# main.net
KiCad netlist of a schematic drawn in Altium Designer
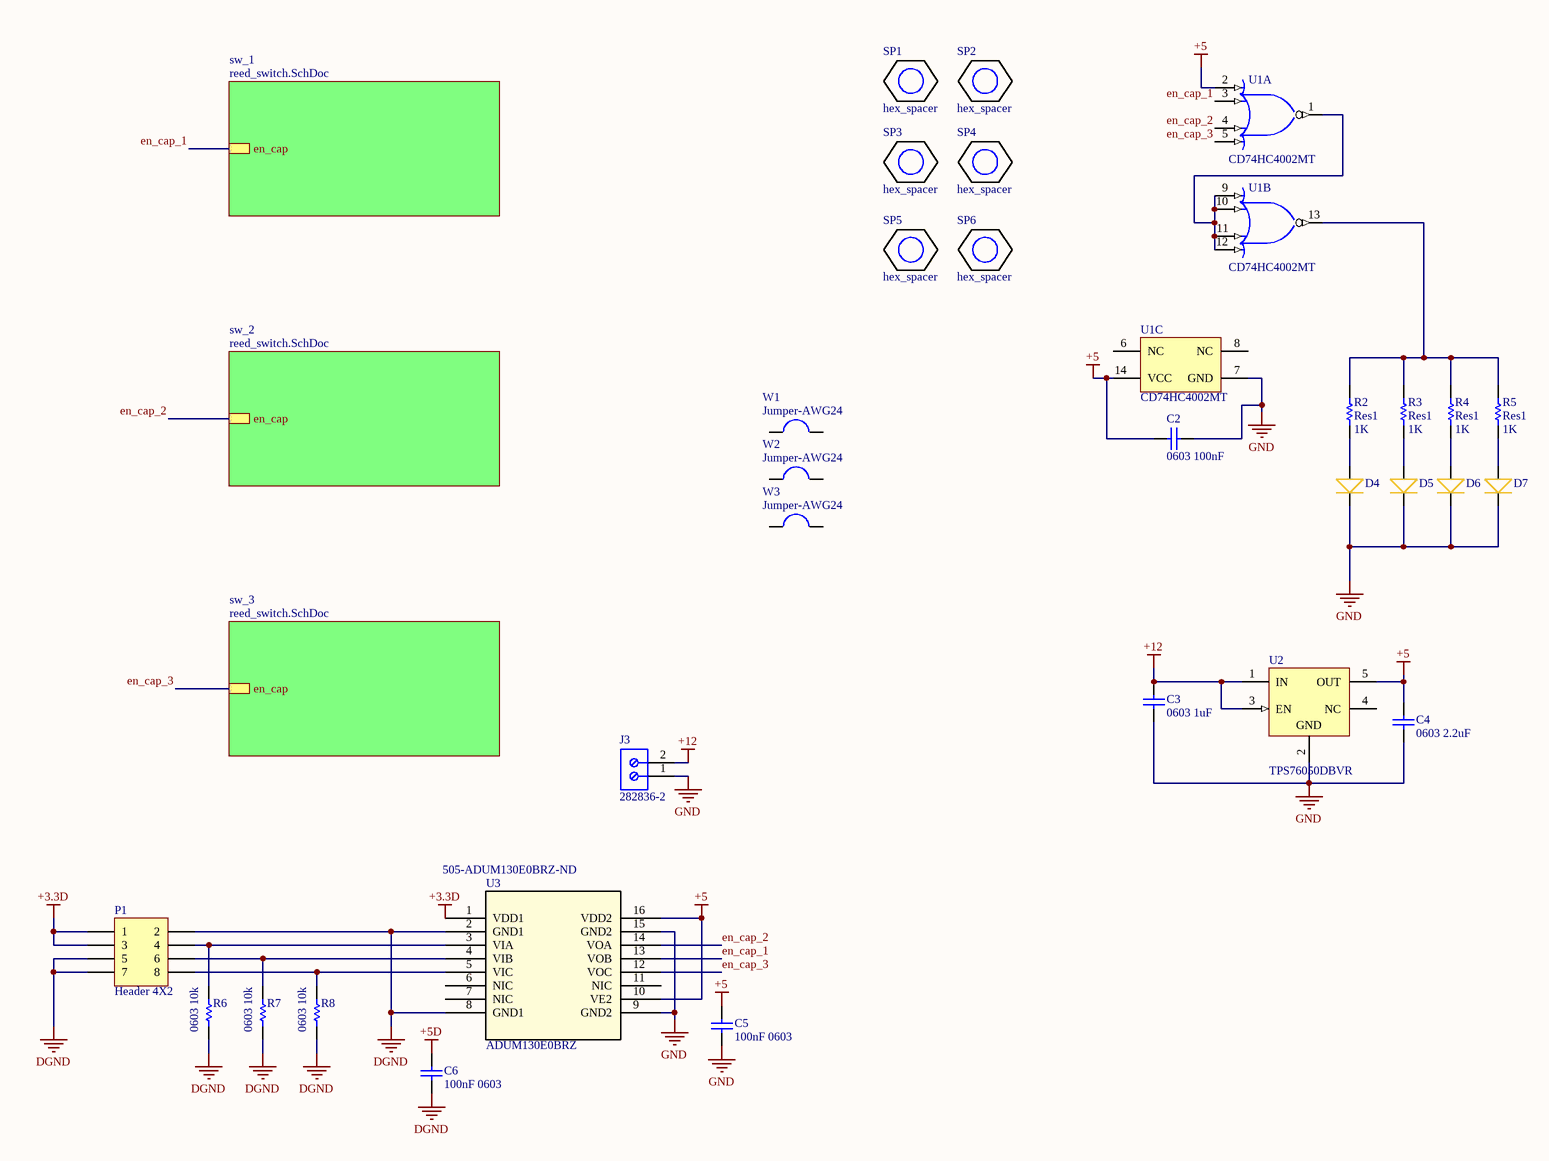
[diagram p0: main.SchDoc]

(export (version "E")
  (design (tool "Eeschema 10.0.6"))
  (components
    (comp (ref "C2")
      (value "0603 100nF")
      (footprint "CAP 0603_1608")
      (description "Capacitor")
      (fields (field (name "PUBLISHER") "Altium Limited"))
      (libsource (lib "Miscellaneous Devices") (part "Cap"))
    )
    (comp (ref "C3")
      (value "0603 1uF")
      (footprint "CAP 0603_1608")
      (description "Capacitor")
      (fields (field (name "PUBLISHER") "Altium Limited"))
      (libsource (lib "Miscellaneous Devices") (part "Cap"))
    )
    (comp (ref "C4")
      (value "0603 2.2uF")
      (footprint "CAP 0603_1608")
      (description "Capacitor")
      (fields (field (name "PUBLISHER") "Altium Limited"))
      (libsource (lib "Miscellaneous Devices") (part "Cap"))
    )
    (comp (ref "C5")
      (value "100nF 0603")
      (footprint "CAP 0603_1608")
      (description "Capacitor")
      (fields (field (name "PUBLISHER") "Altium Limited"))
      (libsource (lib "Miscellaneous Devices") (part "Cap"))
    )
    (comp (ref "C6")
      (value "100nF 0603")
      (footprint "CAP 0603_1608")
      (description "Capacitor")
      (fields (field (name "PUBLISHER") "Altium Limited"))
      (libsource (lib "Miscellaneous Devices") (part "Cap"))
    )
    (comp (ref "D4")
      (value "732-12018-1-ND")
      (footprint "LED_YELLOW_0603")
      (libsource (lib "coil_driver_lib") (part "led_yellow_0603"))
    )
    (comp (ref "D5")
      (value "732-12018-1-ND")
      (footprint "LED_YELLOW_0603")
      (libsource (lib "coil_driver_lib") (part "led_yellow_0603"))
    )
    (comp (ref "D6")
      (value "732-12018-1-ND")
      (footprint "LED_YELLOW_0603")
      (libsource (lib "coil_driver_lib") (part "led_yellow_0603"))
    )
    (comp (ref "D7")
      (value "732-12018-1-ND")
      (footprint "LED_YELLOW_0603")
      (libsource (lib "coil_driver_lib") (part "led_yellow_0603"))
    )
    (comp (ref "J3")
      (value "282836-2")
      (footprint "TECO-282836-2_V")
      (description "Female Header, Pitch 5 mm, 1 x 2 Position, Height 10 mm, Tail Length 3.5 mm, Rohs, Bulk")
      (fields (field (name "VOLTAGE") "300V") (field (name "MANUFACTURER") "TE Connectivity"))
      (libsource (lib "Altium Content Vault") (part "CN-1P-F-TB2"))
    )
    (comp (ref "P1")
      (value "Header 4X2")
      (footprint "HEADER_4_2")
      (description "Header, 4-Pin, Dual row")
      (fields (field (name "PUBLISHER") "Altium Limited"))
      (libsource (lib "Miscellaneous Connectors") (part "Header 4X2"))
    )
    (comp (ref "R2")
      (value "Res1")
      (footprint "RES 0603_1608")
      (description "Resistor")
      (fields (field (name "ALTIUM_VALUE") "1K") (field (name "PUBLISHER") "Altium Limited"))
      (libsource (lib "Miscellaneous Devices") (part "Res1"))
    )
    (comp (ref "R3")
      (value "Res1")
      (footprint "RES 0603_1608")
      (description "Resistor")
      (fields (field (name "ALTIUM_VALUE") "1K") (field (name "PUBLISHER") "Altium Limited"))
      (libsource (lib "Miscellaneous Devices") (part "Res1"))
    )
    (comp (ref "R4")
      (value "Res1")
      (footprint "RES 0603_1608")
      (description "Resistor")
      (fields (field (name "ALTIUM_VALUE") "1K") (field (name "PUBLISHER") "Altium Limited"))
      (libsource (lib "Miscellaneous Devices") (part "Res1"))
    )
    (comp (ref "R5")
      (value "Res1")
      (footprint "RES 0603_1608")
      (description "Resistor")
      (fields (field (name "ALTIUM_VALUE") "1K") (field (name "PUBLISHER") "Altium Limited"))
      (libsource (lib "Miscellaneous Devices") (part "Res1"))
    )
    (comp (ref "R6")
      (value "0603 10k")
      (footprint "RES 0603_1608")
      (description "Resistor")
      (fields (field (name "PUBLISHER") "Altium Limited"))
      (libsource (lib "Miscellaneous Devices") (part "Res1"))
    )
    (comp (ref "R7")
      (value "0603 10k")
      (footprint "RES 0603_1608")
      (description "Resistor")
      (fields (field (name "PUBLISHER") "Altium Limited"))
      (libsource (lib "Miscellaneous Devices") (part "Res1"))
    )
    (comp (ref "R8")
      (value "0603 10k")
      (footprint "RES 0603_1608")
      (description "Resistor")
      (fields (field (name "PUBLISHER") "Altium Limited"))
      (libsource (lib "Miscellaneous Devices") (part "Res1"))
    )
    (comp (ref "SP1")
      (value "hex_spacer")
      (footprint "hex_spacer")
      (libsource (lib "coil_driver_lib") (part "hex_spacer"))
    )
    (comp (ref "SP2")
      (value "hex_spacer")
      (footprint "hex_spacer")
      (libsource (lib "coil_driver_lib") (part "hex_spacer"))
    )
    (comp (ref "SP3")
      (value "hex_spacer")
      (footprint "hex_spacer")
      (libsource (lib "coil_driver_lib") (part "hex_spacer"))
    )
    (comp (ref "SP4")
      (value "hex_spacer")
      (footprint "hex_spacer")
      (libsource (lib "coil_driver_lib") (part "hex_spacer"))
    )
    (comp (ref "SP5")
      (value "hex_spacer")
      (footprint "hex_spacer")
      (libsource (lib "coil_driver_lib") (part "hex_spacer"))
    )
    (comp (ref "SP6")
      (value "hex_spacer")
      (footprint "hex_spacer")
      (libsource (lib "coil_driver_lib") (part "hex_spacer"))
    )
    (comp (ref "U1")
      (value "CD74HC4002MT")
      (footprint "D0014A_N")
      (description "High Speed CMOS Logic Dual 4-Input NOR Gates, D0014A, SMALL T&R")
      (fields
        (field (name "MANUFACTURER") "Texas Instruments")
        (field (name "GENERIC PART NUMBER") "CD74HC4002")
      )
      (libsource (lib "Altium Content Vault") (part "TI-CD_SNX4HC4002-14"))
    )
    (comp (ref "U2")
      (value "TPS76050DBVR")
      (footprint "DBV0005A_L")
      (fields (field (name "MANUFACTURER") "Texas Instruments"))
      (libsource (lib "Altium Content Vault") (part "TI-TXX7XXXX-5"))
    )
    (comp (ref "U3")
      (value "ADUM130E0BRZ")
      (footprint "R_16")
      (description "No Description Available")
      (fields
        (field (name "SUPPLIER PART NUMBER 1") "505-ADUM130E0BRZ-ND")
        (field (name "COPYRIGHT") "Copyright (C) 2021 Ultra Librarian. All rights reserved.")
      )
      (libsource (lib "ADUM130E0BRZ") (part "ADUM130E0BRZ"))
    )
    (comp (ref "W1")
      (value "wire_jumper")
      (footprint "wire_jumper")
      (libsource (lib "coil_driver_lib") (part "wire_jumper"))
    )
    (comp (ref "W2")
      (value "wire_jumper")
      (footprint "wire_jumper")
      (libsource (lib "coil_driver_lib") (part "wire_jumper"))
    )
    (comp (ref "W3")
      (value "wire_jumper")
      (footprint "wire_jumper")
      (libsource (lib "coil_driver_lib") (part "wire_jumper"))
    )
  )
  (nets
    (net (code "1") (name "+3.3D") (class "Default")
      (node (ref "P1") (pin "1") (pinfunction "1_1") (pintype "passive"))
      (node (ref "P1") (pin "3") (pinfunction "3_3") (pintype "passive"))
      (node (ref "U3") (pin "1") (pinfunction "VDD1_1") (pintype "passive"))
    )
    (net (code "2") (name "+5") (class "Default")
      (node (ref "C2") (pin "2") (pinfunction "2_2") (pintype "passive"))
      (node (ref "C4") (pin "2") (pinfunction "2_2") (pintype "passive"))
      (node (ref "C5") (pin "2") (pinfunction "2_2") (pintype "passive"))
      (node (ref "U1") (pin "14") (pinfunction "VCC_14") (pintype "power_in"))
      (node (ref "U1") (pin "2") (pinfunction "1A_2") (pintype "input"))
      (node (ref "U2") (pin "5") (pinfunction "OUT_5") (pintype "power_in"))
      (node (ref "U3") (pin "10") (pinfunction "VE2_10") (pintype "passive"))
      (node (ref "U3") (pin "16") (pinfunction "VDD2_16") (pintype "passive"))
    )
    (net (code "3") (name "+5D") (class "Default")
      (node (ref "C6") (pin "2") (pinfunction "2_2") (pintype "passive"))
    )
    (net (code "4") (name "+12") (class "Default")
      (node (ref "C3") (pin "2") (pinfunction "2_2") (pintype "passive"))
      (node (ref "J3") (pin "2") (pinfunction "2_2") (pintype "passive"))
      (node (ref "U2") (pin "1") (pinfunction "IN_1") (pintype "power_in"))
      (node (ref "U2") (pin "3") (pinfunction "EN_3") (pintype "input"))
    )
    (net (code "5") (name "/en_cap_1") (class "Default")
      (node (ref "U1") (pin "3") (pinfunction "1B_3") (pintype "input"))
      (node (ref "U3") (pin "13") (pinfunction "VOB_13") (pintype "passive"))
    )
    (net (code "6") (name "/en_cap_2") (class "Default")
      (node (ref "U1") (pin "4") (pinfunction "1C_4") (pintype "input"))
      (node (ref "U3") (pin "14") (pinfunction "VOA_14") (pintype "passive"))
    )
    (net (code "7") (name "/en_cap_3") (class "Default")
      (node (ref "U1") (pin "5") (pinfunction "1D_5") (pintype "input"))
      (node (ref "U3") (pin "12") (pinfunction "VOC_12") (pintype "passive"))
    )
    (net (code "8") (name "DGND") (class "Default")
      (node (ref "C6") (pin "1") (pinfunction "1_1") (pintype "passive"))
      (node (ref "P1") (pin "2") (pinfunction "2_2") (pintype "passive"))
      (node (ref "P1") (pin "5") (pinfunction "5_5") (pintype "passive"))
      (node (ref "P1") (pin "7") (pinfunction "7_7") (pintype "passive"))
      (node (ref "R6") (pin "1") (pinfunction "1_1") (pintype "passive"))
      (node (ref "R7") (pin "1") (pinfunction "1_1") (pintype "passive"))
      (node (ref "R8") (pin "1") (pinfunction "1_1") (pintype "passive"))
      (node (ref "U3") (pin "2") (pinfunction "GND1_2") (pintype "passive"))
      (node (ref "U3") (pin "8") (pinfunction "GND1_8") (pintype "passive"))
    )
    (net (code "9") (name "GND") (class "Default")
      (node (ref "C2") (pin "1") (pinfunction "1_1") (pintype "passive"))
      (node (ref "C3") (pin "1") (pinfunction "1_1") (pintype "passive"))
      (node (ref "C4") (pin "1") (pinfunction "1_1") (pintype "passive"))
      (node (ref "C5") (pin "1") (pinfunction "1_1") (pintype "passive"))
      (node (ref "D4") (pin "C") (pinfunction "C_C") (pintype "passive"))
      (node (ref "D5") (pin "C") (pinfunction "C_C") (pintype "passive"))
      (node (ref "D6") (pin "C") (pinfunction "C_C") (pintype "passive"))
      (node (ref "D7") (pin "C") (pinfunction "C_C") (pintype "passive"))
      (node (ref "J3") (pin "1") (pinfunction "1_1") (pintype "passive"))
      (node (ref "U1") (pin "7") (pinfunction "GND_7") (pintype "power_in"))
      (node (ref "U2") (pin "2") (pinfunction "GND_2") (pintype "power_in"))
      (node (ref "U3") (pin "15") (pinfunction "GND2_15") (pintype "passive"))
      (node (ref "U3") (pin "9") (pinfunction "GND2_9") (pintype "passive"))
    )
    (net (code "10") (name "Net-(D4-PadA)") (class "Default")
      (node (ref "D4") (pin "A") (pinfunction "A_A") (pintype "passive"))
      (node (ref "R2") (pin "1") (pinfunction "1_1") (pintype "passive"))
    )
    (net (code "11") (name "Net-(D5-PadA)") (class "Default")
      (node (ref "D5") (pin "A") (pinfunction "A_A") (pintype "passive"))
      (node (ref "R3") (pin "1") (pinfunction "1_1") (pintype "passive"))
    )
    (net (code "12") (name "Net-(D6-PadA)") (class "Default")
      (node (ref "D6") (pin "A") (pinfunction "A_A") (pintype "passive"))
      (node (ref "R4") (pin "1") (pinfunction "1_1") (pintype "passive"))
    )
    (net (code "13") (name "Net-(D7-PadA)") (class "Default")
      (node (ref "D7") (pin "A") (pinfunction "A_A") (pintype "passive"))
      (node (ref "R5") (pin "1") (pinfunction "1_1") (pintype "passive"))
    )
    (net (code "14") (name "Net-(U1A-1Y)") (class "Default")
      (node (ref "U1") (pin "1") (pinfunction "1Y_1") (pintype "output"))
      (node (ref "U1") (pin "10") (pinfunction "2B_10") (pintype "input"))
      (node (ref "U1") (pin "11") (pinfunction "2C_11") (pintype "input"))
      (node (ref "U1") (pin "12") (pinfunction "2D_12") (pintype "input"))
      (node (ref "U1") (pin "9") (pinfunction "2A_9") (pintype "input"))
    )
    (net (code "15") (name "Net-(U1B-2Y)") (class "Default")
      (node (ref "R2") (pin "2") (pinfunction "2_2") (pintype "passive"))
      (node (ref "R3") (pin "2") (pinfunction "2_2") (pintype "passive"))
      (node (ref "R4") (pin "2") (pinfunction "2_2") (pintype "passive"))
      (node (ref "R5") (pin "2") (pinfunction "2_2") (pintype "passive"))
      (node (ref "U1") (pin "13") (pinfunction "2Y_13") (pintype "output"))
    )
    (net (code "16") (name "Net-(U3-VIA)") (class "Default")
      (node (ref "P1") (pin "4") (pinfunction "4_4") (pintype "passive"))
      (node (ref "R6") (pin "2") (pinfunction "2_2") (pintype "passive"))
      (node (ref "U3") (pin "3") (pinfunction "VIA_3") (pintype "passive"))
    )
    (net (code "17") (name "Net-(U3-VIB)") (class "Default")
      (node (ref "P1") (pin "6") (pinfunction "6_6") (pintype "passive"))
      (node (ref "R7") (pin "2") (pinfunction "2_2") (pintype "passive"))
      (node (ref "U3") (pin "4") (pinfunction "VIB_4") (pintype "passive"))
    )
    (net (code "18") (name "Net-(U3-VIC)") (class "Default")
      (node (ref "P1") (pin "8") (pinfunction "8_8") (pintype "passive"))
      (node (ref "R8") (pin "2") (pinfunction "2_2") (pintype "passive"))
      (node (ref "U3") (pin "5") (pinfunction "VIC_5") (pintype "passive"))
    )
    (net (code "19") (name "unconnected-(U1C-NC-Pad6)") (class "Default")
      (node (ref "U1") (pin "6") (pinfunction "NC_6") (pintype "passive"))
    )
    (net (code "20") (name "unconnected-(U1C-NC-Pad8)") (class "Default")
      (node (ref "U1") (pin "8") (pinfunction "NC_8") (pintype "passive"))
    )
    (net (code "21") (name "unconnected-(U2-NC-Pad4)") (class "Default")
      (node (ref "U2") (pin "4") (pinfunction "NC_4") (pintype "passive"))
    )
    (net (code "22") (name "unconnected-(U3-NIC-Pad6)") (class "Default")
      (node (ref "U3") (pin "6") (pinfunction "NIC_6") (pintype "passive"))
    )
    (net (code "23") (name "unconnected-(U3-NIC-Pad7)") (class "Default")
      (node (ref "U3") (pin "7") (pinfunction "NIC_7") (pintype "passive"))
    )
    (net (code "24") (name "unconnected-(U3-NIC-Pad11)") (class "Default")
      (node (ref "U3") (pin "11") (pinfunction "NIC_11") (pintype "passive"))
    )
    (net (code "25") (name "unconnected-(W1-Pad1)") (class "Default")
      (node (ref "W1") (pin "1") (pinfunction "1_1") (pintype "passive"))
    )
    (net (code "26") (name "unconnected-(W1-Pad2)") (class "Default")
      (node (ref "W1") (pin "2") (pinfunction "2_2") (pintype "passive"))
    )
    (net (code "27") (name "unconnected-(W2-Pad1)") (class "Default")
      (node (ref "W2") (pin "1") (pinfunction "1_1") (pintype "passive"))
    )
    (net (code "28") (name "unconnected-(W2-Pad2)") (class "Default")
      (node (ref "W2") (pin "2") (pinfunction "2_2") (pintype "passive"))
    )
    (net (code "29") (name "unconnected-(W3-Pad1)") (class "Default")
      (node (ref "W3") (pin "1") (pinfunction "1_1") (pintype "passive"))
    )
    (net (code "30") (name "unconnected-(W3-Pad2)") (class "Default")
      (node (ref "W3") (pin "2") (pinfunction "2_2") (pintype "passive"))
    )
  )
)
